# AM335x_EVM_PMconnect_Rev2.net
KiCad netlist of a schematic drawn in Altium Designer
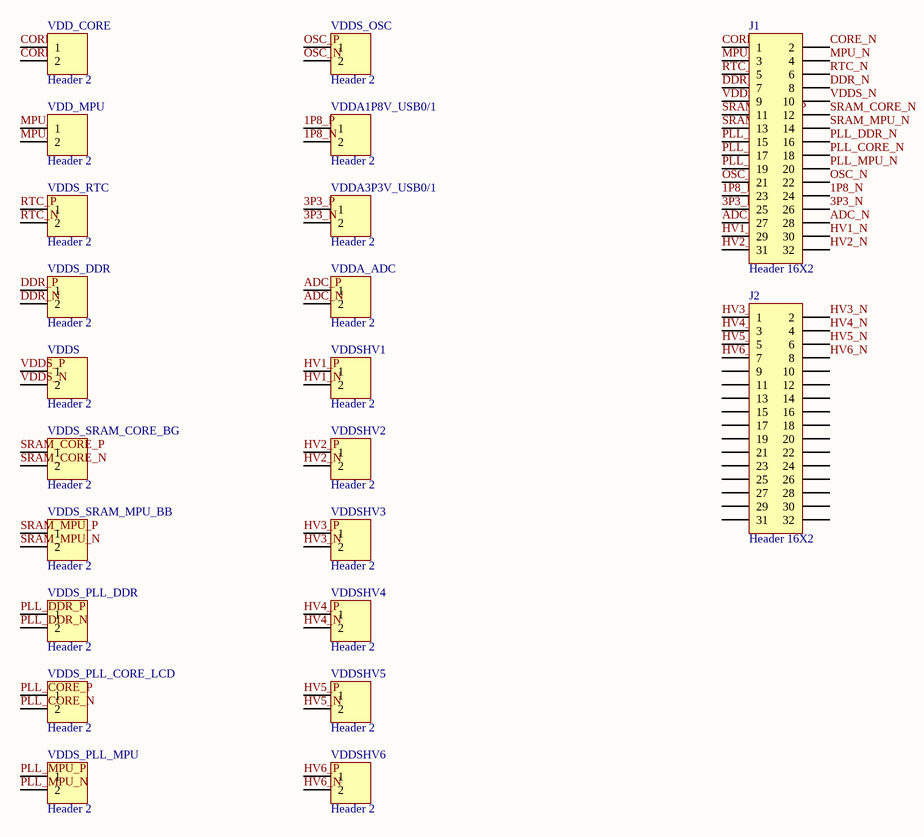
[diagram p0: AM335x_EVM_PMconnect_Rev2.SchDoc]

(export (version "E")
  (design (tool "Eeschema 10.0.6"))
  (components
    (comp (ref "J1")
      (value "Header 16X2")
      (footprint "HDR2X16")
      (description "Header, 16-Pin, Dual row")
      (fields (field (name "PUBLISHER") "Altium Limited"))
      (libsource (lib "Miscellaneous Connectors") (part "Header 16X2"))
    )
    (comp (ref "J2")
      (value "Header 16X2")
      (footprint "HDR2X16")
      (description "Header, 16-Pin, Dual row")
      (fields (field (name "PUBLISHER") "Altium Limited"))
      (libsource (lib "Miscellaneous Connectors") (part "Header 16X2"))
    )
    (comp (ref "VDDA1P8V_USB0/1")
      (value "Header 2")
      (footprint "HDR1X2")
      (description "Header, 2-Pin")
      (fields (field (name "PUBLISHER") "Altium Limited"))
      (libsource (lib "Miscellaneous Connectors") (part "Header 2"))
    )
    (comp (ref "VDDA3P3V_USB0/1")
      (value "Header 2")
      (footprint "HDR1X2")
      (description "Header, 2-Pin")
      (fields (field (name "PUBLISHER") "Altium Limited"))
      (libsource (lib "Miscellaneous Connectors") (part "Header 2"))
    )
    (comp (ref "VDDA_ADC")
      (value "Header 2")
      (footprint "HDR1X2")
      (description "Header, 2-Pin")
      (fields (field (name "PUBLISHER") "Altium Limited"))
      (libsource (lib "Miscellaneous Connectors") (part "Header 2"))
    )
    (comp (ref "VDDS")
      (value "Header 2")
      (footprint "HDR1X2")
      (description "Header, 2-Pin")
      (fields (field (name "PUBLISHER") "Altium Limited"))
      (libsource (lib "Miscellaneous Connectors") (part "Header 2"))
    )
    (comp (ref "VDDSHV1")
      (value "Header 2")
      (footprint "HDR1X2")
      (description "Header, 2-Pin")
      (fields (field (name "PUBLISHER") "Altium Limited"))
      (libsource (lib "Miscellaneous Connectors") (part "Header 2"))
    )
    (comp (ref "VDDSHV2")
      (value "Header 2")
      (footprint "HDR1X2")
      (description "Header, 2-Pin")
      (fields (field (name "PUBLISHER") "Altium Limited"))
      (libsource (lib "Miscellaneous Connectors") (part "Header 2"))
    )
    (comp (ref "VDDSHV3")
      (value "Header 2")
      (footprint "HDR1X2")
      (description "Header, 2-Pin")
      (fields (field (name "PUBLISHER") "Altium Limited"))
      (libsource (lib "Miscellaneous Connectors") (part "Header 2"))
    )
    (comp (ref "VDDSHV4")
      (value "Header 2")
      (footprint "HDR1X2")
      (description "Header, 2-Pin")
      (fields (field (name "PUBLISHER") "Altium Limited"))
      (libsource (lib "Miscellaneous Connectors") (part "Header 2"))
    )
    (comp (ref "VDDSHV5")
      (value "Header 2")
      (footprint "HDR1X2")
      (description "Header, 2-Pin")
      (fields (field (name "PUBLISHER") "Altium Limited"))
      (libsource (lib "Miscellaneous Connectors") (part "Header 2"))
    )
    (comp (ref "VDDSHV6")
      (value "Header 2")
      (footprint "HDR1X2")
      (description "Header, 2-Pin")
      (fields (field (name "PUBLISHER") "Altium Limited"))
      (libsource (lib "Miscellaneous Connectors") (part "Header 2"))
    )
    (comp (ref "VDDS_DDR")
      (value "Header 2")
      (footprint "HDR1X2")
      (description "Header, 2-Pin")
      (fields (field (name "PUBLISHER") "Altium Limited"))
      (libsource (lib "Miscellaneous Connectors") (part "Header 2"))
    )
    (comp (ref "VDDS_OSC")
      (value "Header 2")
      (footprint "HDR1X2")
      (description "Header, 2-Pin")
      (fields (field (name "PUBLISHER") "Altium Limited"))
      (libsource (lib "Miscellaneous Connectors") (part "Header 2"))
    )
    (comp (ref "VDDS_PLL_CORE_LCD")
      (value "Header 2")
      (footprint "HDR1X2")
      (description "Header, 2-Pin")
      (fields (field (name "PUBLISHER") "Altium Limited"))
      (libsource (lib "Miscellaneous Connectors") (part "Header 2"))
    )
    (comp (ref "VDDS_PLL_DDR")
      (value "Header 2")
      (footprint "HDR1X2")
      (description "Header, 2-Pin")
      (fields (field (name "PUBLISHER") "Altium Limited"))
      (libsource (lib "Miscellaneous Connectors") (part "Header 2"))
    )
    (comp (ref "VDDS_PLL_MPU")
      (value "Header 2")
      (footprint "HDR1X2")
      (description "Header, 2-Pin")
      (fields (field (name "PUBLISHER") "Altium Limited"))
      (libsource (lib "Miscellaneous Connectors") (part "Header 2"))
    )
    (comp (ref "VDDS_RTC")
      (value "Header 2")
      (footprint "HDR1X2")
      (description "Header, 2-Pin")
      (fields (field (name "PUBLISHER") "Altium Limited"))
      (libsource (lib "Miscellaneous Connectors") (part "Header 2"))
    )
    (comp (ref "VDDS_SRAM_CORE_BG")
      (value "Header 2")
      (footprint "HDR1X2")
      (description "Header, 2-Pin")
      (fields (field (name "PUBLISHER") "Altium Limited"))
      (libsource (lib "Miscellaneous Connectors") (part "Header 2"))
    )
    (comp (ref "VDDS_SRAM_MPU_BB")
      (value "Header 2")
      (footprint "HDR1X2")
      (description "Header, 2-Pin")
      (fields (field (name "PUBLISHER") "Altium Limited"))
      (libsource (lib "Miscellaneous Connectors") (part "Header 2"))
    )
    (comp (ref "VDD_CORE")
      (value "Header 2")
      (footprint "HDR1X2")
      (description "Header, 2-Pin")
      (fields (field (name "PUBLISHER") "Altium Limited"))
      (libsource (lib "Miscellaneous Connectors") (part "Header 2"))
    )
    (comp (ref "VDD_MPU")
      (value "Header 2")
      (footprint "HDR1X2")
      (description "Header, 2-Pin")
      (fields (field (name "PUBLISHER") "Altium Limited"))
      (libsource (lib "Miscellaneous Connectors") (part "Header 2"))
    )
  )
  (nets
    (net (code "1") (name "/1P8_N") (class "Default")
      (node (ref "J1") (pin "24") (pinfunction "24_24") (pintype "passive"))
      (node (ref "VDDA1P8V_USB0/1") (pin "2") (pinfunction "2_2") (pintype "passive"))
    )
    (net (code "2") (name "/1P8_P") (class "Default")
      (node (ref "J1") (pin "23") (pinfunction "23_23") (pintype "passive"))
      (node (ref "VDDA1P8V_USB0/1") (pin "1") (pinfunction "1_1") (pintype "passive"))
    )
    (net (code "3") (name "/3P3_N") (class "Default")
      (node (ref "J1") (pin "26") (pinfunction "26_26") (pintype "passive"))
      (node (ref "VDDA3P3V_USB0/1") (pin "2") (pinfunction "2_2") (pintype "passive"))
    )
    (net (code "4") (name "/3P3_P") (class "Default")
      (node (ref "J1") (pin "25") (pinfunction "25_25") (pintype "passive"))
      (node (ref "VDDA3P3V_USB0/1") (pin "1") (pinfunction "1_1") (pintype "passive"))
    )
    (net (code "5") (name "/ADC_N") (class "Default")
      (node (ref "J1") (pin "28") (pinfunction "28_28") (pintype "passive"))
      (node (ref "VDDA_ADC") (pin "2") (pinfunction "2_2") (pintype "passive"))
    )
    (net (code "6") (name "/ADC_P") (class "Default")
      (node (ref "J1") (pin "27") (pinfunction "27_27") (pintype "passive"))
      (node (ref "VDDA_ADC") (pin "1") (pinfunction "1_1") (pintype "passive"))
    )
    (net (code "7") (name "/CORE_N") (class "Default")
      (node (ref "J1") (pin "2") (pinfunction "2_2") (pintype "passive"))
      (node (ref "VDD_CORE") (pin "2") (pinfunction "2_2") (pintype "passive"))
    )
    (net (code "8") (name "/CORE_P") (class "Default")
      (node (ref "J1") (pin "1") (pinfunction "1_1") (pintype "passive"))
      (node (ref "VDD_CORE") (pin "1") (pinfunction "1_1") (pintype "passive"))
    )
    (net (code "9") (name "/DDR_N") (class "Default")
      (node (ref "J1") (pin "8") (pinfunction "8_8") (pintype "passive"))
      (node (ref "VDDS_DDR") (pin "2") (pinfunction "2_2") (pintype "passive"))
    )
    (net (code "10") (name "/DDR_P") (class "Default")
      (node (ref "J1") (pin "7") (pinfunction "7_7") (pintype "passive"))
      (node (ref "VDDS_DDR") (pin "1") (pinfunction "1_1") (pintype "passive"))
    )
    (net (code "11") (name "/HV1_N") (class "Default")
      (node (ref "J1") (pin "30") (pinfunction "30_30") (pintype "passive"))
      (node (ref "VDDSHV1") (pin "2") (pinfunction "2_2") (pintype "passive"))
    )
    (net (code "12") (name "/HV1_P") (class "Default")
      (node (ref "J1") (pin "29") (pinfunction "29_29") (pintype "passive"))
      (node (ref "VDDSHV1") (pin "1") (pinfunction "1_1") (pintype "passive"))
    )
    (net (code "13") (name "/HV2_N") (class "Default")
      (node (ref "J1") (pin "32") (pinfunction "32_32") (pintype "passive"))
      (node (ref "VDDSHV2") (pin "2") (pinfunction "2_2") (pintype "passive"))
    )
    (net (code "14") (name "/HV2_P") (class "Default")
      (node (ref "J1") (pin "31") (pinfunction "31_31") (pintype "passive"))
      (node (ref "VDDSHV2") (pin "1") (pinfunction "1_1") (pintype "passive"))
    )
    (net (code "15") (name "/HV3_N") (class "Default")
      (node (ref "J2") (pin "2") (pinfunction "2_2") (pintype "passive"))
      (node (ref "VDDSHV3") (pin "2") (pinfunction "2_2") (pintype "passive"))
    )
    (net (code "16") (name "/HV3_P") (class "Default")
      (node (ref "J2") (pin "1") (pinfunction "1_1") (pintype "passive"))
      (node (ref "VDDSHV3") (pin "1") (pinfunction "1_1") (pintype "passive"))
    )
    (net (code "17") (name "/HV4_N") (class "Default")
      (node (ref "J2") (pin "4") (pinfunction "4_4") (pintype "passive"))
      (node (ref "VDDSHV4") (pin "2") (pinfunction "2_2") (pintype "passive"))
    )
    (net (code "18") (name "/HV4_P") (class "Default")
      (node (ref "J2") (pin "3") (pinfunction "3_3") (pintype "passive"))
      (node (ref "VDDSHV4") (pin "1") (pinfunction "1_1") (pintype "passive"))
    )
    (net (code "19") (name "/HV5_N") (class "Default")
      (node (ref "J2") (pin "6") (pinfunction "6_6") (pintype "passive"))
      (node (ref "VDDSHV5") (pin "2") (pinfunction "2_2") (pintype "passive"))
    )
    (net (code "20") (name "/HV5_P") (class "Default")
      (node (ref "J2") (pin "5") (pinfunction "5_5") (pintype "passive"))
      (node (ref "VDDSHV5") (pin "1") (pinfunction "1_1") (pintype "passive"))
    )
    (net (code "21") (name "/HV6_N") (class "Default")
      (node (ref "J2") (pin "8") (pinfunction "8_8") (pintype "passive"))
      (node (ref "VDDSHV6") (pin "2") (pinfunction "2_2") (pintype "passive"))
    )
    (net (code "22") (name "/HV6_P") (class "Default")
      (node (ref "J2") (pin "7") (pinfunction "7_7") (pintype "passive"))
      (node (ref "VDDSHV6") (pin "1") (pinfunction "1_1") (pintype "passive"))
    )
    (net (code "23") (name "/MPU_N") (class "Default")
      (node (ref "J1") (pin "4") (pinfunction "4_4") (pintype "passive"))
      (node (ref "VDD_MPU") (pin "2") (pinfunction "2_2") (pintype "passive"))
    )
    (net (code "24") (name "/MPU_P") (class "Default")
      (node (ref "J1") (pin "3") (pinfunction "3_3") (pintype "passive"))
      (node (ref "VDD_MPU") (pin "1") (pinfunction "1_1") (pintype "passive"))
    )
    (net (code "25") (name "/OSC_N") (class "Default")
      (node (ref "J1") (pin "22") (pinfunction "22_22") (pintype "passive"))
      (node (ref "VDDS_OSC") (pin "2") (pinfunction "2_2") (pintype "passive"))
    )
    (net (code "26") (name "/OSC_P") (class "Default")
      (node (ref "J1") (pin "21") (pinfunction "21_21") (pintype "passive"))
      (node (ref "VDDS_OSC") (pin "1") (pinfunction "1_1") (pintype "passive"))
    )
    (net (code "27") (name "/PLL_CORE_N") (class "Default")
      (node (ref "J1") (pin "18") (pinfunction "18_18") (pintype "passive"))
      (node (ref "VDDS_PLL_CORE_LCD") (pin "2") (pinfunction "2_2") (pintype "passive"))
    )
    (net (code "28") (name "/PLL_CORE_P") (class "Default")
      (node (ref "J1") (pin "17") (pinfunction "17_17") (pintype "passive"))
      (node (ref "VDDS_PLL_CORE_LCD") (pin "1") (pinfunction "1_1") (pintype "passive"))
    )
    (net (code "29") (name "/PLL_DDR_N") (class "Default")
      (node (ref "J1") (pin "16") (pinfunction "16_16") (pintype "passive"))
      (node (ref "VDDS_PLL_DDR") (pin "2") (pinfunction "2_2") (pintype "passive"))
    )
    (net (code "30") (name "/PLL_DDR_P") (class "Default")
      (node (ref "J1") (pin "15") (pinfunction "15_15") (pintype "passive"))
      (node (ref "VDDS_PLL_DDR") (pin "1") (pinfunction "1_1") (pintype "passive"))
    )
    (net (code "31") (name "/PLL_MPU_N") (class "Default")
      (node (ref "J1") (pin "20") (pinfunction "20_20") (pintype "passive"))
      (node (ref "VDDS_PLL_MPU") (pin "2") (pinfunction "2_2") (pintype "passive"))
    )
    (net (code "32") (name "/PLL_MPU_P") (class "Default")
      (node (ref "J1") (pin "19") (pinfunction "19_19") (pintype "passive"))
      (node (ref "VDDS_PLL_MPU") (pin "1") (pinfunction "1_1") (pintype "passive"))
    )
    (net (code "33") (name "/RTC_N") (class "Default")
      (node (ref "J1") (pin "6") (pinfunction "6_6") (pintype "passive"))
      (node (ref "VDDS_RTC") (pin "2") (pinfunction "2_2") (pintype "passive"))
    )
    (net (code "34") (name "/RTC_P") (class "Default")
      (node (ref "J1") (pin "5") (pinfunction "5_5") (pintype "passive"))
      (node (ref "VDDS_RTC") (pin "1") (pinfunction "1_1") (pintype "passive"))
    )
    (net (code "35") (name "/SRAM_CORE_N") (class "Default")
      (node (ref "J1") (pin "12") (pinfunction "12_12") (pintype "passive"))
      (node (ref "VDDS_SRAM_CORE_BG") (pin "2") (pinfunction "2_2") (pintype "passive"))
    )
    (net (code "36") (name "/SRAM_CORE_P") (class "Default")
      (node (ref "J1") (pin "11") (pinfunction "11_11") (pintype "passive"))
      (node (ref "VDDS_SRAM_CORE_BG") (pin "1") (pinfunction "1_1") (pintype "passive"))
    )
    (net (code "37") (name "/SRAM_MPU_N") (class "Default")
      (node (ref "J1") (pin "14") (pinfunction "14_14") (pintype "passive"))
      (node (ref "VDDS_SRAM_MPU_BB") (pin "2") (pinfunction "2_2") (pintype "passive"))
    )
    (net (code "38") (name "/SRAM_MPU_P") (class "Default")
      (node (ref "J1") (pin "13") (pinfunction "13_13") (pintype "passive"))
      (node (ref "VDDS_SRAM_MPU_BB") (pin "1") (pinfunction "1_1") (pintype "passive"))
    )
    (net (code "39") (name "/VDDS_N") (class "Default")
      (node (ref "J1") (pin "10") (pinfunction "10_10") (pintype "passive"))
      (node (ref "VDDS") (pin "2") (pinfunction "2_2") (pintype "passive"))
    )
    (net (code "40") (name "/VDDS_P") (class "Default")
      (node (ref "J1") (pin "9") (pinfunction "9_9") (pintype "passive"))
      (node (ref "VDDS") (pin "1") (pinfunction "1_1") (pintype "passive"))
    )
    (net (code "41") (name "unconnected-(J2-Pad9)") (class "Default")
      (node (ref "J2") (pin "9") (pinfunction "9_9") (pintype "passive"))
    )
    (net (code "42") (name "unconnected-(J2-Pad10)") (class "Default")
      (node (ref "J2") (pin "10") (pinfunction "10_10") (pintype "passive"))
    )
    (net (code "43") (name "unconnected-(J2-Pad11)") (class "Default")
      (node (ref "J2") (pin "11") (pinfunction "11_11") (pintype "passive"))
    )
    (net (code "44") (name "unconnected-(J2-Pad12)") (class "Default")
      (node (ref "J2") (pin "12") (pinfunction "12_12") (pintype "passive"))
    )
    (net (code "45") (name "unconnected-(J2-Pad13)") (class "Default")
      (node (ref "J2") (pin "13") (pinfunction "13_13") (pintype "passive"))
    )
    (net (code "46") (name "unconnected-(J2-Pad14)") (class "Default")
      (node (ref "J2") (pin "14") (pinfunction "14_14") (pintype "passive"))
    )
    (net (code "47") (name "unconnected-(J2-Pad15)") (class "Default")
      (node (ref "J2") (pin "15") (pinfunction "15_15") (pintype "passive"))
    )
    (net (code "48") (name "unconnected-(J2-Pad16)") (class "Default")
      (node (ref "J2") (pin "16") (pinfunction "16_16") (pintype "passive"))
    )
    (net (code "49") (name "unconnected-(J2-Pad17)") (class "Default")
      (node (ref "J2") (pin "17") (pinfunction "17_17") (pintype "passive"))
    )
    (net (code "50") (name "unconnected-(J2-Pad18)") (class "Default")
      (node (ref "J2") (pin "18") (pinfunction "18_18") (pintype "passive"))
    )
    (net (code "51") (name "unconnected-(J2-Pad19)") (class "Default")
      (node (ref "J2") (pin "19") (pinfunction "19_19") (pintype "passive"))
    )
    (net (code "52") (name "unconnected-(J2-Pad20)") (class "Default")
      (node (ref "J2") (pin "20") (pinfunction "20_20") (pintype "passive"))
    )
    (net (code "53") (name "unconnected-(J2-Pad21)") (class "Default")
      (node (ref "J2") (pin "21") (pinfunction "21_21") (pintype "passive"))
    )
    (net (code "54") (name "unconnected-(J2-Pad22)") (class "Default")
      (node (ref "J2") (pin "22") (pinfunction "22_22") (pintype "passive"))
    )
    (net (code "55") (name "unconnected-(J2-Pad23)") (class "Default")
      (node (ref "J2") (pin "23") (pinfunction "23_23") (pintype "passive"))
    )
    (net (code "56") (name "unconnected-(J2-Pad24)") (class "Default")
      (node (ref "J2") (pin "24") (pinfunction "24_24") (pintype "passive"))
    )
    (net (code "57") (name "unconnected-(J2-Pad25)") (class "Default")
      (node (ref "J2") (pin "25") (pinfunction "25_25") (pintype "passive"))
    )
    (net (code "58") (name "unconnected-(J2-Pad26)") (class "Default")
      (node (ref "J2") (pin "26") (pinfunction "26_26") (pintype "passive"))
    )
    (net (code "59") (name "unconnected-(J2-Pad27)") (class "Default")
      (node (ref "J2") (pin "27") (pinfunction "27_27") (pintype "passive"))
    )
    (net (code "60") (name "unconnected-(J2-Pad28)") (class "Default")
      (node (ref "J2") (pin "28") (pinfunction "28_28") (pintype "passive"))
    )
    (net (code "61") (name "unconnected-(J2-Pad29)") (class "Default")
      (node (ref "J2") (pin "29") (pinfunction "29_29") (pintype "passive"))
    )
    (net (code "62") (name "unconnected-(J2-Pad30)") (class "Default")
      (node (ref "J2") (pin "30") (pinfunction "30_30") (pintype "passive"))
    )
    (net (code "63") (name "unconnected-(J2-Pad31)") (class "Default")
      (node (ref "J2") (pin "31") (pinfunction "31_31") (pintype "passive"))
    )
    (net (code "64") (name "unconnected-(J2-Pad32)") (class "Default")
      (node (ref "J2") (pin "32") (pinfunction "32_32") (pintype "passive"))
    )
  )
)
